# Power_Architecture.net
KiCad netlist of a schematic drawn in Altium Designer
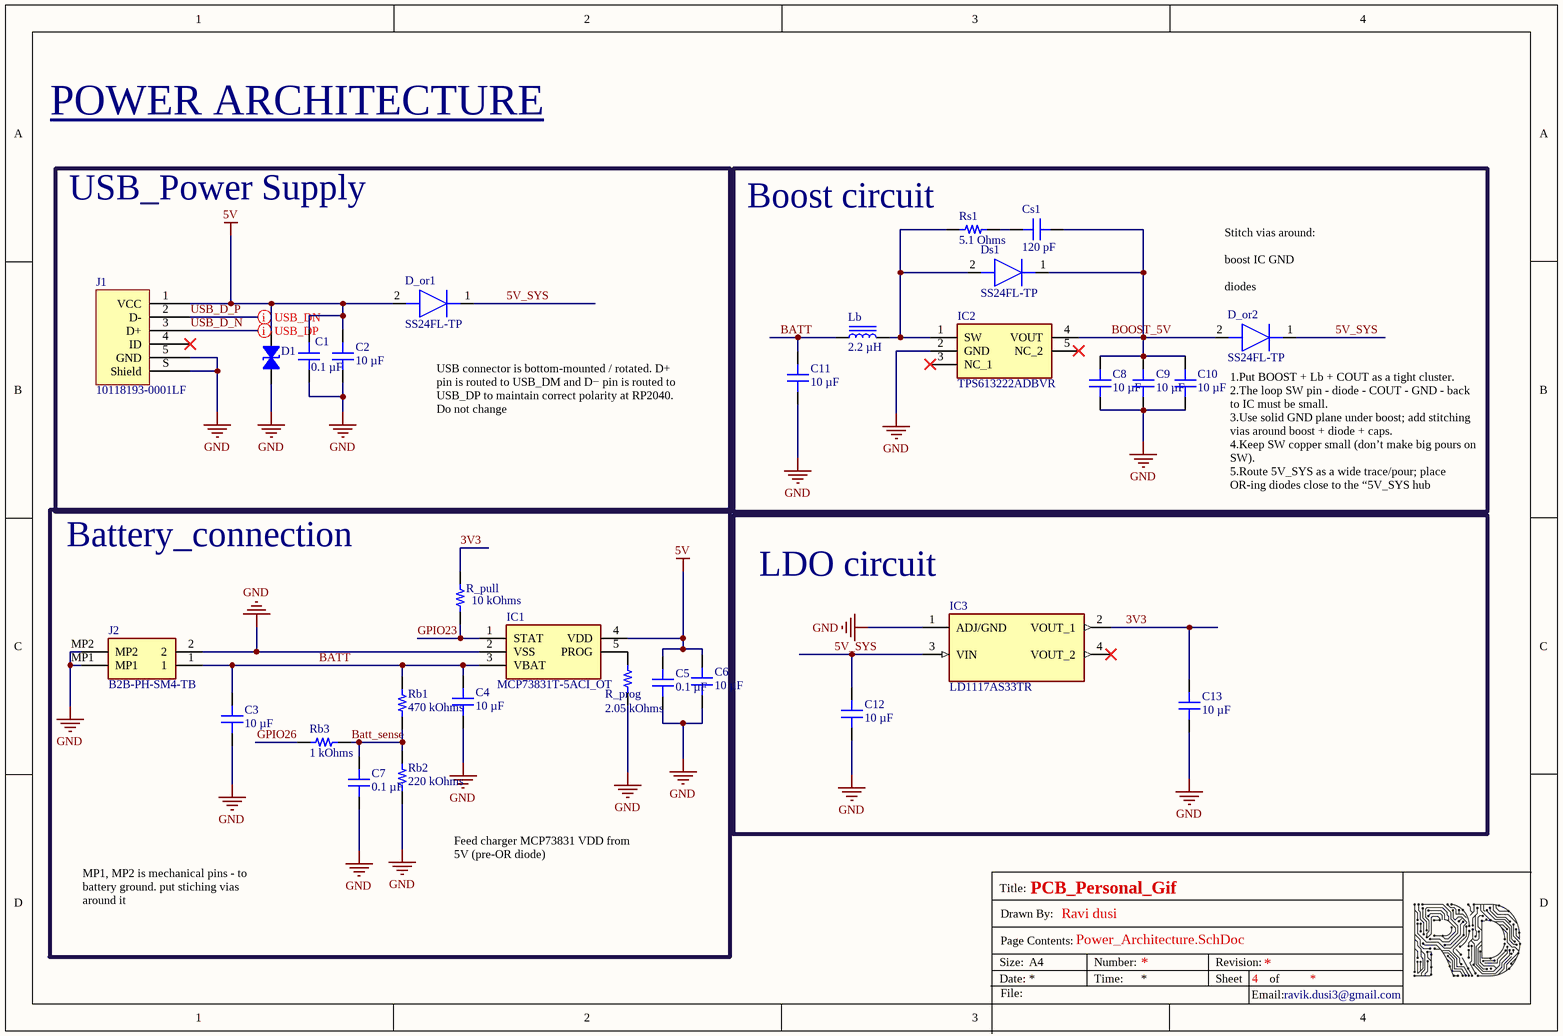
[diagram p0: Power_Architecture.SchDoc]

(export (version "E")
  (design (tool "Eeschema 10.0.6"))
  (components
    (comp (ref "C1")
      (value "0.1 µF")
      (footprint "CAP 0402_1005")
      (description "CAP CER 0402 0.1UF 16V X7R 10%")
      (fields (field (name "PART NUMBER") "C0402C104K4RECAUTO") (field (name "MANUFACTURER") "KEMET"))
      (libsource (lib "Celestial Altium Library - altium_library") (part "Capacitor"))
    )
    (comp (ref "C2")
      (value "10 µF")
      (footprint "CAP 0402_1005")
      (description "CAP CER 10UF 10V X5R 0402")
      (fields
        (field (name "PART NUMBER") "CL05A106MP8NUB8")
        (field (name "MANUFACTURER") "Samsung Electro-Mechanics")
      )
      (libsource (lib "Celestial Altium Library - altium_library") (part "Capacitor"))
    )
    (comp (ref "C3")
      (value "10 µF")
      (footprint "CAP 0402_1005")
      (description "CAP CER 10UF 10V X5R 0402")
      (fields
        (field (name "PART NUMBER") "CL05A106MP8NUB8")
        (field (name "CAPACITANCE") "10 µF")
        (field (name "MANUFACTURER") "Samsung Electro-Mechanics")
      )
      (libsource (lib "Celestial Altium Library - altium_library (1)") (part "Capacitor"))
    )
    (comp (ref "C4")
      (value "10 µF")
      (footprint "CAP 0402_1005")
      (description "CAP CER 10UF 10V X5R 0402")
      (fields
        (field (name "PART NUMBER") "CL05A106MP8NUB8")
        (field (name "CAPACITANCE") "10 µF")
        (field (name "MANUFACTURER") "Samsung Electro-Mechanics")
      )
      (libsource (lib "Celestial Altium Library - altium_library (1)") (part "Capacitor"))
    )
    (comp (ref "C5")
      (value "0.1 µF")
      (footprint "CAP 0402_1005")
      (description "CAP CER 0402 0.1UF 16V X7R 10%")
      (fields
        (field (name "PART NUMBER") "C0402C104K4RECAUTO")
        (field (name "CAPACITANCE") "0.1 µF")
        (field (name "MANUFACTURER") "KEMET")
      )
      (libsource (lib "Celestial Altium Library - altium_library (1)") (part "Capacitor"))
    )
    (comp (ref "C6")
      (value "10 µF")
      (footprint "CAP 0402_1005")
      (description "CAP CER 10UF 10V X5R 0402")
      (fields
        (field (name "PART NUMBER") "CL05A106MP8NUB8")
        (field (name "CAPACITANCE") "10 µF")
        (field (name "MANUFACTURER") "Samsung Electro-Mechanics")
      )
      (libsource (lib "Celestial Altium Library - altium_library (1)") (part "Capacitor"))
    )
    (comp (ref "C7")
      (value "0.1 µF")
      (footprint "CAP 0402_1005")
      (description "CAP CER 0402 0.1UF 16V X7R 10%")
      (fields
        (field (name "PART NUMBER") "C0402C104K4RECAUTO")
        (field (name "CAPACITANCE") "0.1 µF")
        (field (name "MANUFACTURER") "KEMET")
      )
      (libsource (lib "Celestial Altium Library - altium_library (1)") (part "Capacitor"))
    )
    (comp (ref "C8")
      (value "10 µF")
      (footprint "CAP 0402_1005")
      (description "CAP CER 10UF 10V X5R 0402")
      (fields
        (field (name "PART NUMBER") "CL05A106MP8NUB8")
        (field (name "CAPACITANCE") "10 µF")
        (field (name "MANUFACTURER") "Samsung Electro-Mechanics")
      )
      (libsource (lib "Celestial Altium Library - altium_library (1)") (part "Capacitor"))
    )
    (comp (ref "C9")
      (value "10 µF")
      (footprint "CAP 0402_1005")
      (description "CAP CER 10UF 10V X5R 0402")
      (fields
        (field (name "PART NUMBER") "CL05A106MP8NUB8")
        (field (name "CAPACITANCE") "10 µF")
        (field (name "MANUFACTURER") "Samsung Electro-Mechanics")
      )
      (libsource (lib "Celestial Altium Library - altium_library (1)") (part "Capacitor"))
    )
    (comp (ref "C10")
      (value "10 µF")
      (footprint "CAP 0402_1005")
      (description "CAP CER 10UF 10V X5R 0402")
      (fields
        (field (name "PART NUMBER") "CL05A106MP8NUB8")
        (field (name "CAPACITANCE") "10 µF")
        (field (name "MANUFACTURER") "Samsung Electro-Mechanics")
      )
      (libsource (lib "Celestial Altium Library - altium_library (1)") (part "Capacitor"))
    )
    (comp (ref "C11")
      (value "10 µF")
      (footprint "CAP 0402_1005")
      (description "CAP CER 10UF 10V X5R 0402")
      (fields
        (field (name "PART NUMBER") "CL05A106MP8NUB8")
        (field (name "CAPACITANCE") "10 µF")
        (field (name "MANUFACTURER") "Samsung Electro-Mechanics")
      )
      (libsource (lib "Celestial Altium Library - altium_library (1)") (part "Capacitor"))
    )
    (comp (ref "C12")
      (value "10 µF")
      (footprint "CAP 0402_1005")
      (description "CAP CER 10UF 10V X5R 0402")
      (fields
        (field (name "PART NUMBER") "CL05A106MP8NUB8")
        (field (name "CAPACITANCE") "10 µF")
        (field (name "MANUFACTURER") "Samsung Electro-Mechanics")
      )
      (libsource (lib "Celestial Altium Library - altium_library (1)") (part "Capacitor"))
    )
    (comp (ref "C13")
      (value "10 µF")
      (footprint "CAP 0402_1005")
      (description "CAP CER 10UF 10V X5R 0402")
      (fields
        (field (name "PART NUMBER") "CL05A106MP8NUB8")
        (field (name "CAPACITANCE") "10 µF")
        (field (name "MANUFACTURER") "Samsung Electro-Mechanics")
      )
      (libsource (lib "Celestial Altium Library - altium_library (1)") (part "Capacitor"))
    )
    (comp (ref "Cs1")
      (value "120 pF")
      (footprint "CAP 0402_1005")
      (description "CAP CER 120PF 50V C0G 0402")
      (fields
        (field (name "PART NUMBER") "CGA2B2C0G1H121J050BA")
        (field (name "CAPACITANCE") "120 pF")
        (field (name "MANUFACTURER") "TDK Corporation")
      )
      (libsource (lib "Celestial Altium Library - altium_library (1)") (part "Capacitor"))
    )
    (comp (ref "D1")
      (value "PGSMAJ12CA E3G")
      (footprint "DO214AC SMA")
      (description "DIODE, TVS, BIDIRECTIONAL")
      (fields (field (name "MANUFACTURER") "Taiwan Semiconductor Corporation"))
      (libsource (lib "Celestial Altium Library - altium_library") (part "Diode TVS"))
    )
    (comp (ref "Ds1")
      (value "SS24FL-TP")
      (footprint "SamacSys:SODFL5026X125N")
      (description "Diode")
      (fields (field (name "MOUSER PART NUMBER") "833-SS24FL-TP"))
      (libsource (lib "*") (part "SS24FL-TP"))
    )
    (comp (ref "D_or1")
      (value "SS24FL-TP")
      (footprint "SamacSys:SODFL5026X125N")
      (description "Diode")
      (fields (field (name "MOUSER PART NUMBER") "833-SS24FL-TP"))
      (libsource (lib "*") (part "SS24FL-TP"))
    )
    (comp (ref "D_or2")
      (value "SS24FL-TP")
      (footprint "SamacSys:SODFL5026X125N")
      (description "Diode")
      (fields (field (name "MOUSER PART NUMBER") "833-SS24FL-TP"))
      (libsource (lib "*") (part "SS24FL-TP"))
    )
    (comp (ref "IC1")
      (value "MCP73831T-5ACI_OT")
      (footprint "SamacSys:SOT95P270X145-5N")
      (description "Integrated Circuit")
      (fields
        (field (name "MANUFACTURER_PART_NUMBER") "MCP73831T-5ACI/OT")
        (field (name "MOUSER PART NUMBER") "579-MCP73831T5ACIOT")
      )
      (libsource (lib "*") (part "MCP73831T-5ACI_OT"))
    )
    (comp (ref "IC2")
      (value "TPS613222ADBVR")
      (footprint "SamacSys:SOT95P280X145-5N")
      (description "Integrated Circuit")
      (fields (field (name "MOUSER PART NUMBER") "595-TPS613222ADBVR"))
      (libsource (lib "*") (part "TPS613222ADBVR"))
    )
    (comp (ref "IC3")
      (value "LD1117AS33TR")
      (footprint "SamacSys:SOT230P700X190-4N")
      (description "Power Supply")
      (fields (field (name "MOUSER PART NUMBER") "511-LD1117AS33"))
      (libsource (lib "SamacSys") (part "LD1117AS33TR"))
    )
    (comp (ref "J1")
      (value "10118193-0001LF")
      (footprint "FCI USB 10118193-0001LF")
      (description "CONN RCPT USB2.0 MICRO B SMD R/A")
      (fields (field (name "MANUFACTURER") "Amphenol ICC (FCI)"))
      (libsource (lib "Celestial Altium Library - altium_library") (part "USB 2.0 Type B Micro"))
    )
    (comp (ref "J2")
      (value "B2B-PH-SM4-TB")
      (footprint "SamacSys:B2BPHSM4TB")
      (description "Connector")
      (libsource (lib "*") (part "B2B-PH-SM4-TB"))
    )
    (comp (ref "Lb")
      (value "2.2 µH")
      (footprint "BOURNS SRP5030T")
      (description "FIXED IND 2.2UH 5.5A 35 MOHM SMD")
      (fields (field (name "PART NUMBER") "SRP5030T-2R2M") (field (name "MANUFACTURER") "Bourns Inc."))
      (libsource (lib "Celestial Altium Library - altium_library (1)") (part "Inductor"))
    )
    (comp (ref "Rb1")
      (value "470 kOhms")
      (footprint "RES 0402_1005")
      (description "RES 470K OHM 1% 1/8W 0402")
      (fields
        (field (name "PART NUMBER") "CRGP0402F470K")
        (field (name "MANUFACTURER") "TE Connectivity Passive Product")
      )
      (libsource (lib "Celestial Altium Library - altium_library (1)") (part "Resistor"))
    )
    (comp (ref "Rb2")
      (value "220 kOhms")
      (footprint "YAGEO RES 0402_1005")
      (description "RES 220K OHM 1% 1/16W 0402")
      (fields (field (name "PART NUMBER") "RC0402FR-07220KL") (field (name "MANUFACTURER") "Yageo"))
      (libsource (lib "Celestial Altium Library - altium_library (1)") (part "Resistor"))
    )
    (comp (ref "Rb3")
      (value "1 kOhms")
      (footprint "YAGEO RES 0402_1005")
      (description "RES SMD 1K OHM 0.1% 1/16W 0402")
      (fields (field (name "PART NUMBER") "AT0402BRD071KL") (field (name "MANUFACTURER") "Yageo"))
      (libsource (lib "Celestial Altium Library - altium_library (1)") (part "Resistor"))
    )
    (comp (ref "Rs1")
      (value "5.1 Ohms")
      (footprint "YAGEO RES 0402_1005")
      (description "RES 5.1 OHM 5% 1/16W 0402")
      (fields (field (name "PART NUMBER") "RC0402JR-075R1L") (field (name "MANUFACTURER") "Yageo"))
      (libsource (lib "Celestial Altium Library - altium_library (1)") (part "Resistor"))
    )
    (comp (ref "R_prog")
      (value "2.05 kOhms")
      (footprint "RES 0402_1005")
      (description "RES SMD 2.05KOHM 0.1% 1/16W 0402")
      (fields
        (field (name "PART NUMBER") "CPF0402B2K05E1")
        (field (name "MANUFACTURER") "TE Connectivity Passive Product")
      )
      (libsource (lib "Celestial Altium Library - altium_library (1)") (part "Resistor"))
    )
    (comp (ref "R_pull")
      (value "10 kOhms")
      (footprint "RES 0402_1005")
      (description "RES 10K OHM 0.1% 1/10W 0402")
      (fields
        (field (name "PART NUMBER") "RP73PF1E10KBTD")
        (field (name "MANUFACTURER") "TE Connectivity Passive Product")
      )
      (libsource (lib "Celestial Altium Library - altium_library (1)") (part "Resistor"))
    )
  )
  (nets
    (net (code "1") (name "/3V3") (class "Default")
      (node (ref "C13") (pin "2") (pinfunction "2_2") (pintype "passive"))
      (node (ref "IC3") (pin "2") (pinfunction "VOUT_1_2") (pintype "output"))
      (node (ref "R_pull") (pin "2") (pinfunction "2_2") (pintype "passive"))
    )
    (net (code "2") (name "/5V_SYS") (class "Default")
      (node (ref "C12") (pin "2") (pinfunction "2_2") (pintype "passive"))
      (node (ref "D_or1") (pin "1") (pinfunction "K_1") (pintype "passive"))
      (node (ref "D_or2") (pin "1") (pinfunction "K_1") (pintype "passive"))
      (node (ref "IC3") (pin "3") (pinfunction "VIN_3") (pintype "input"))
    )
    (net (code "3") (name "/BATT") (class "Default")
      (node (ref "C11") (pin "2") (pinfunction "2_2") (pintype "passive"))
      (node (ref "C3") (pin "2") (pinfunction "2_2") (pintype "passive"))
      (node (ref "C4") (pin "2") (pinfunction "2_2") (pintype "passive"))
      (node (ref "IC1") (pin "3") (pinfunction "VBAT_3") (pintype "passive"))
      (node (ref "J2") (pin "1") (pinfunction "1_1") (pintype "passive"))
      (node (ref "Lb") (pin "1") (pinfunction "1_1") (pintype "passive"))
      (node (ref "Rb1") (pin "2") (pinfunction "2_2") (pintype "passive"))
    )
    (net (code "4") (name "/BOOST_5V") (class "Default")
      (node (ref "C10") (pin "1") (pinfunction "1_1") (pintype "passive"))
      (node (ref "C8") (pin "1") (pinfunction "1_1") (pintype "passive"))
      (node (ref "C9") (pin "1") (pinfunction "1_1") (pintype "passive"))
      (node (ref "Cs1") (pin "2") (pinfunction "2_2") (pintype "passive"))
      (node (ref "D_or2") (pin "2") (pinfunction "A_2") (pintype "passive"))
      (node (ref "Ds1") (pin "1") (pinfunction "K_1") (pintype "passive"))
      (node (ref "IC2") (pin "4") (pinfunction "VOUT_4") (pintype "passive"))
    )
    (net (code "5") (name "/Batt_sense") (class "Default")
      (node (ref "C7") (pin "2") (pinfunction "2_2") (pintype "passive"))
      (node (ref "Rb1") (pin "1") (pinfunction "1_1") (pintype "passive"))
      (node (ref "Rb2") (pin "2") (pinfunction "2_2") (pintype "passive"))
      (node (ref "Rb3") (pin "2") (pinfunction "2_2") (pintype "passive"))
    )
    (net (code "6") (name "/GPIO23") (class "Default")
      (node (ref "IC1") (pin "1") (pinfunction "STAT_1") (pintype "passive"))
      (node (ref "R_pull") (pin "1") (pinfunction "1_1") (pintype "passive"))
    )
    (net (code "7") (name "/GPIO26") (class "Default")
      (node (ref "Rb3") (pin "1") (pinfunction "1_1") (pintype "passive"))
    )
    (net (code "8") (name "/USB_D_N") (class "Default")
      (node (ref "J1") (pin "3") (pinfunction "D+_3") (pintype "passive"))
    )
    (net (code "9") (name "/USB_D_P") (class "Default")
      (node (ref "J1") (pin "2") (pinfunction "D-_2") (pintype "passive"))
    )
    (net (code "10") (name "5V") (class "Default")
      (node (ref "C1") (pin "2") (pinfunction "2_2") (pintype "passive"))
      (node (ref "C2") (pin "2") (pinfunction "2_2") (pintype "passive"))
      (node (ref "C5") (pin "2") (pinfunction "2_2") (pintype "passive"))
      (node (ref "C6") (pin "2") (pinfunction "2_2") (pintype "passive"))
      (node (ref "D1") (pin "2") (pinfunction "2_2") (pintype "passive"))
      (node (ref "D_or1") (pin "2") (pinfunction "A_2") (pintype "passive"))
      (node (ref "IC1") (pin "4") (pinfunction "VDD_4") (pintype "passive"))
      (node (ref "J1") (pin "1") (pinfunction "VCC_1") (pintype "passive"))
    )
    (net (code "11") (name "GND") (class "Default")
      (node (ref "C1") (pin "1") (pinfunction "1_1") (pintype "passive"))
      (node (ref "C10") (pin "2") (pinfunction "2_2") (pintype "passive"))
      (node (ref "C11") (pin "1") (pinfunction "1_1") (pintype "passive"))
      (node (ref "C12") (pin "1") (pinfunction "1_1") (pintype "passive"))
      (node (ref "C13") (pin "1") (pinfunction "1_1") (pintype "passive"))
      (node (ref "C2") (pin "1") (pinfunction "1_1") (pintype "passive"))
      (node (ref "C3") (pin "1") (pinfunction "1_1") (pintype "passive"))
      (node (ref "C4") (pin "1") (pinfunction "1_1") (pintype "passive"))
      (node (ref "C5") (pin "1") (pinfunction "1_1") (pintype "passive"))
      (node (ref "C6") (pin "1") (pinfunction "1_1") (pintype "passive"))
      (node (ref "C7") (pin "1") (pinfunction "1_1") (pintype "passive"))
      (node (ref "C8") (pin "2") (pinfunction "2_2") (pintype "passive"))
      (node (ref "C9") (pin "2") (pinfunction "2_2") (pintype "passive"))
      (node (ref "D1") (pin "1") (pinfunction "1_1") (pintype "passive"))
      (node (ref "IC1") (pin "2") (pinfunction "VSS_2") (pintype "passive"))
      (node (ref "IC2") (pin "2") (pinfunction "GND_2") (pintype "passive"))
      (node (ref "IC3") (pin "1") (pinfunction "ADJ/GND_1") (pintype "power_in"))
      (node (ref "J1") (pin "5") (pinfunction "GND_5") (pintype "passive"))
      (node (ref "J1") (pin "S") (pinfunction "Shield_S") (pintype "passive"))
      (node (ref "J2") (pin "2") (pinfunction "2_2") (pintype "passive"))
      (node (ref "J2") (pin "MP1") (pinfunction "MP1_MP1") (pintype "passive"))
      (node (ref "J2") (pin "MP2") (pinfunction "MP2_MP2") (pintype "passive"))
      (node (ref "R_prog") (pin "1") (pinfunction "1_1") (pintype "passive"))
      (node (ref "Rb2") (pin "1") (pinfunction "1_1") (pintype "passive"))
    )
    (net (code "12") (name "Net-(Cs1-Pad1)") (class "Default")
      (node (ref "Cs1") (pin "1") (pinfunction "1_1") (pintype "passive"))
      (node (ref "Rs1") (pin "2") (pinfunction "2_2") (pintype "passive"))
    )
    (net (code "13") (name "Net-(Ds1-A)") (class "Default")
      (node (ref "Ds1") (pin "2") (pinfunction "A_2") (pintype "passive"))
      (node (ref "IC2") (pin "1") (pinfunction "SW_1") (pintype "passive"))
      (node (ref "Lb") (pin "2") (pinfunction "2_2") (pintype "passive"))
      (node (ref "Rs1") (pin "1") (pinfunction "1_1") (pintype "passive"))
    )
    (net (code "14") (name "Net-(IC1-PROG)") (class "Default")
      (node (ref "IC1") (pin "5") (pinfunction "PROG_5") (pintype "passive"))
      (node (ref "R_prog") (pin "2") (pinfunction "2_2") (pintype "passive"))
    )
    (net (code "15") (name "unconnected-(IC2-NC_1-Pad3)") (class "Default")
      (node (ref "IC2") (pin "3") (pinfunction "NC_1_3") (pintype "passive+no_connect"))
    )
    (net (code "16") (name "unconnected-(IC2-NC_2-Pad5)") (class "Default")
      (node (ref "IC2") (pin "5") (pinfunction "NC_2_5") (pintype "passive+no_connect"))
    )
    (net (code "17") (name "unconnected-(IC3-VOUT_2-Pad4)") (class "Default")
      (node (ref "IC3") (pin "4") (pinfunction "VOUT_2_4") (pintype "output+no_connect"))
    )
    (net (code "18") (name "unconnected-(J1-ID-Pad4)") (class "Default")
      (node (ref "J1") (pin "4") (pinfunction "ID_4") (pintype "passive+no_connect"))
    )
  )
)
